# chassis_ctrl.net
KiCad netlist of a schematic drawn in EAGLE
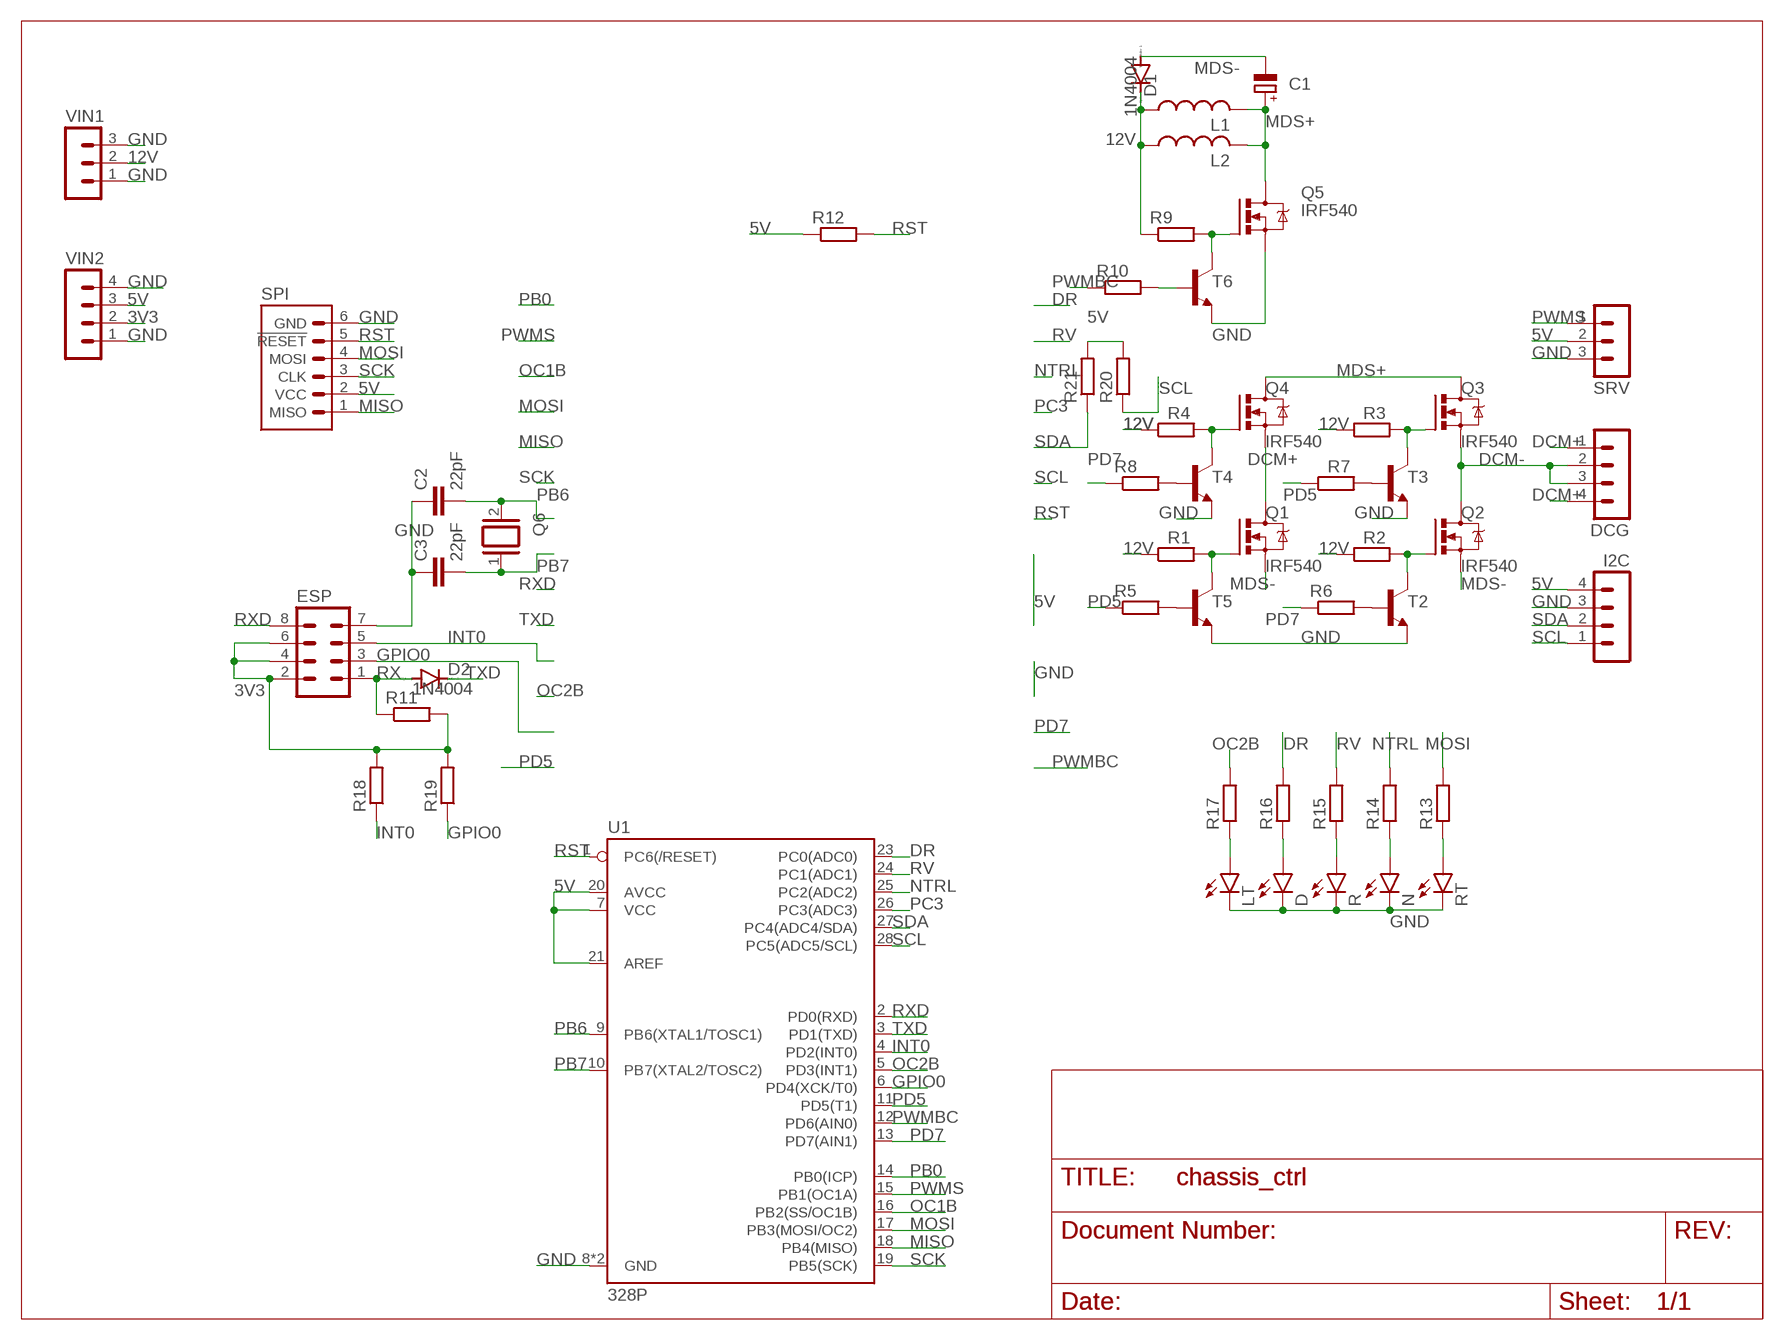
[diagram p0: schematic, sheet 1]

(export (version "E")
  (design (tool "Eeschema 10.0.6"))
  (components
    (comp (ref "C1")
      (value "CPOL-EUE5-10.5")
      (footprint "eagle-import:E5-10,5")
      (libsource (lib "eagle-import") (part "CPOL-EUE5-10.5"))
    )
    (comp (ref "C2")
      (value "22pF")
      (footprint "eagle-import:CAP-PTH-2.54")
      (libsource (lib "eagle-import") (part "22PF-PTH-2.54MM-200V-5%"))
    )
    (comp (ref "C3")
      (value "22pF")
      (footprint "eagle-import:CAP-PTH-2.54")
      (libsource (lib "eagle-import") (part "22PF-PTH-2.54MM-200V-5%"))
    )
    (comp (ref "D")
      (value "LED5MM")
      (footprint "eagle-import:LED5MM")
      (libsource (lib "eagle-import") (part "LED5MM"))
    )
    (comp (ref "D1")
      (value "1N4004")
      (footprint "eagle-import:DO41-10")
      (libsource (lib "eagle-import") (part "1N4004"))
    )
    (comp (ref "D2")
      (value "1N4004")
      (footprint "eagle-import:DO41-10")
      (libsource (lib "eagle-import") (part "1N4004"))
    )
    (comp (ref "DCG")
      (value "MA04-1")
      (footprint "eagle-import:MA04-1")
      (libsource (lib "eagle-import") (part "MA04-1"))
    )
    (comp (ref "ESP")
      (value "MA04-2")
      (footprint "eagle-import:MA04-2")
      (libsource (lib "eagle-import") (part "MA04-2"))
    )
    (comp (ref "I2C")
      (value "MA04-1")
      (footprint "eagle-import:MA04-1")
      (libsource (lib "eagle-import") (part "MA04-1"))
    )
    (comp (ref "L1")
      (value "L-US0204V")
      (footprint "eagle-import:0204V")
      (libsource (lib "eagle-import") (part "L-US0204V"))
    )
    (comp (ref "L2")
      (value "L-US0204V")
      (footprint "eagle-import:0204V")
      (libsource (lib "eagle-import") (part "L-US0204V"))
    )
    (comp (ref "LT")
      (value "LED5MM")
      (footprint "eagle-import:LED5MM")
      (libsource (lib "eagle-import") (part "LED5MM"))
    )
    (comp (ref "N")
      (value "LED5MM")
      (footprint "eagle-import:LED5MM")
      (libsource (lib "eagle-import") (part "LED5MM"))
    )
    (comp (ref "Q1")
      (value "IRF540")
      (footprint "eagle-import:TO220BV")
      (libsource (lib "eagle-import") (part "IRF540"))
    )
    (comp (ref "Q2")
      (value "IRF540")
      (footprint "eagle-import:TO220BV")
      (libsource (lib "eagle-import") (part "IRF540"))
    )
    (comp (ref "Q3")
      (value "IRF540")
      (footprint "eagle-import:TO220BV")
      (libsource (lib "eagle-import") (part "IRF540"))
    )
    (comp (ref "Q4")
      (value "IRF540")
      (footprint "eagle-import:TO220BV")
      (libsource (lib "eagle-import") (part "IRF540"))
    )
    (comp (ref "Q5")
      (value "IRF540")
      (footprint "eagle-import:TO220BV")
      (libsource (lib "eagle-import") (part "IRF540"))
    )
    (comp (ref "Q6")
      (value "XTAL/S")
      (footprint "eagle-import:QS")
      (libsource (lib "eagle-import") (part "XTAL/S"))
    )
    (comp (ref "R")
      (value "LED5MM")
      (footprint "eagle-import:LED5MM")
      (libsource (lib "eagle-import") (part "LED5MM"))
    )
    (comp (ref "R1")
      (value "R-EU_0207/10")
      (footprint "eagle-import:0207_10")
      (libsource (lib "eagle-import") (part "R-EU_0207/10"))
    )
    (comp (ref "R2")
      (value "R-EU_0207/10")
      (footprint "eagle-import:0207_10")
      (libsource (lib "eagle-import") (part "R-EU_0207/10"))
    )
    (comp (ref "R3")
      (value "R-EU_0207/10")
      (footprint "eagle-import:0207_10")
      (libsource (lib "eagle-import") (part "R-EU_0207/10"))
    )
    (comp (ref "R4")
      (value "R-EU_0207/10")
      (footprint "eagle-import:0207_10")
      (libsource (lib "eagle-import") (part "R-EU_0207/10"))
    )
    (comp (ref "R5")
      (value "R-EU_0207/10")
      (footprint "eagle-import:0207_10")
      (libsource (lib "eagle-import") (part "R-EU_0207/10"))
    )
    (comp (ref "R6")
      (value "R-EU_0207/10")
      (footprint "eagle-import:0207_10")
      (libsource (lib "eagle-import") (part "R-EU_0207/10"))
    )
    (comp (ref "R7")
      (value "R-EU_0207/10")
      (footprint "eagle-import:0207_10")
      (libsource (lib "eagle-import") (part "R-EU_0207/10"))
    )
    (comp (ref "R8")
      (value "R-EU_0207/10")
      (footprint "eagle-import:0207_10")
      (libsource (lib "eagle-import") (part "R-EU_0207/10"))
    )
    (comp (ref "R9")
      (value "R-EU_0207/10")
      (footprint "eagle-import:0207_10")
      (libsource (lib "eagle-import") (part "R-EU_0207/10"))
    )
    (comp (ref "R10")
      (value "R-EU_0207/10")
      (footprint "eagle-import:0207_10")
      (libsource (lib "eagle-import") (part "R-EU_0207/10"))
    )
    (comp (ref "R11")
      (value "R-EU_0207/10")
      (footprint "eagle-import:0207_10")
      (libsource (lib "eagle-import") (part "R-EU_0207/10"))
    )
    (comp (ref "R12")
      (value "R-EU_0207/10")
      (footprint "eagle-import:0207_10")
      (libsource (lib "eagle-import") (part "R-EU_0207/10"))
    )
    (comp (ref "R13")
      (value "R-EU_0207/10")
      (footprint "eagle-import:0207_10")
      (libsource (lib "eagle-import") (part "R-EU_0207/10"))
    )
    (comp (ref "R14")
      (value "R-EU_0207/10")
      (footprint "eagle-import:0207_10")
      (libsource (lib "eagle-import") (part "R-EU_0207/10"))
    )
    (comp (ref "R15")
      (value "R-EU_0207/10")
      (footprint "eagle-import:0207_10")
      (libsource (lib "eagle-import") (part "R-EU_0207/10"))
    )
    (comp (ref "R16")
      (value "R-EU_0207/10")
      (footprint "eagle-import:0207_10")
      (libsource (lib "eagle-import") (part "R-EU_0207/10"))
    )
    (comp (ref "R17")
      (value "R-EU_0207/10")
      (footprint "eagle-import:0207_10")
      (libsource (lib "eagle-import") (part "R-EU_0207/10"))
    )
    (comp (ref "R18")
      (value "R-EU_0207/10")
      (footprint "eagle-import:0207_10")
      (libsource (lib "eagle-import") (part "R-EU_0207/10"))
    )
    (comp (ref "R19")
      (value "R-EU_0207/10")
      (footprint "eagle-import:0207_10")
      (libsource (lib "eagle-import") (part "R-EU_0207/10"))
    )
    (comp (ref "R20")
      (value "R-EU_0207/10")
      (footprint "eagle-import:0207_10")
      (libsource (lib "eagle-import") (part "R-EU_0207/10"))
    )
    (comp (ref "R21")
      (value "R-EU_0207/10")
      (footprint "eagle-import:0207_10")
      (libsource (lib "eagle-import") (part "R-EU_0207/10"))
    )
    (comp (ref "RT")
      (value "LED5MM")
      (footprint "eagle-import:LED5MM")
      (libsource (lib "eagle-import") (part "LED5MM"))
    )
    (comp (ref "SPI")
      (value "MISO_MOSITHT_100MIL")
      (footprint "eagle-import:PINHEADER_2R03_100MIL")
      (libsource (lib "eagle-import") (part "MISO_MOSITHT_100MIL"))
    )
    (comp (ref "SRV")
      (value "MA03-1")
      (footprint "eagle-import:MA03-1")
      (libsource (lib "eagle-import") (part "MA03-1"))
    )
    (comp (ref "T2")
      (value "2N2222-NPN-TO92-EBC")
      (footprint "eagle-import:TO92-EBC")
      (libsource (lib "eagle-import") (part "-NPN-TO92-EBC2N2222"))
    )
    (comp (ref "T3")
      (value "2N2222-NPN-TO92-EBC")
      (footprint "eagle-import:TO92-EBC")
      (libsource (lib "eagle-import") (part "-NPN-TO92-EBC2N2222"))
    )
    (comp (ref "T4")
      (value "2N2222-NPN-TO92-EBC")
      (footprint "eagle-import:TO92-EBC")
      (libsource (lib "eagle-import") (part "-NPN-TO92-EBC2N2222"))
    )
    (comp (ref "T5")
      (value "2N2222-NPN-TO92-EBC")
      (footprint "eagle-import:TO92-EBC")
      (libsource (lib "eagle-import") (part "-NPN-TO92-EBC2N2222"))
    )
    (comp (ref "T6")
      (value "2N2222-NPN-TO92-EBC")
      (footprint "eagle-import:TO92-EBC")
      (libsource (lib "eagle-import") (part "-NPN-TO92-EBC2N2222"))
    )
    (comp (ref "U1")
      (value "328P")
      (footprint "eagle-import:DIP28")
      (libsource (lib "eagle-import") (part "ATMEGA328P_PDIP"))
    )
    (comp (ref "VIN1")
      (value "MA03-1")
      (footprint "eagle-import:MA03-1")
      (libsource (lib "eagle-import") (part "MA03-1"))
    )
    (comp (ref "VIN2")
      (value "MA04-1")
      (footprint "eagle-import:MA04-1")
      (libsource (lib "eagle-import") (part "MA04-1"))
    )
  )
  (nets
    (net (code "1") (name "/3V3") (class "Default")
      (node (ref "ESP") (pin "2") (pinfunction "2_2") (pintype "passive"))
      (node (ref "ESP") (pin "4") (pinfunction "4_4") (pintype "passive"))
      (node (ref "ESP") (pin "6") (pinfunction "6_6") (pintype "passive"))
      (node (ref "R11") (pin "2") (pinfunction "2_2") (pintype "passive"))
      (node (ref "R18") (pin "2") (pinfunction "2_2") (pintype "passive"))
      (node (ref "R19") (pin "2") (pinfunction "2_2") (pintype "passive"))
      (node (ref "VIN2") (pin "2") (pinfunction "2_2") (pintype "passive"))
    )
    (net (code "2") (name "/5V") (class "Default")
      (node (ref "I2C") (pin "4") (pinfunction "4_4") (pintype "passive"))
      (node (ref "R12") (pin "1") (pinfunction "1_1") (pintype "passive"))
      (node (ref "R20") (pin "2") (pinfunction "2_2") (pintype "passive"))
      (node (ref "R21") (pin "2") (pinfunction "2_2") (pintype "passive"))
      (node (ref "SPI") (pin "2") (pinfunction "VCC_2") (pintype "power_in"))
      (node (ref "SRV") (pin "2") (pinfunction "2_2") (pintype "passive"))
      (node (ref "U1") (pin "20") (pinfunction "AVCC_20") (pintype "bidirectional"))
      (node (ref "U1") (pin "21") (pinfunction "AREF_21") (pintype "bidirectional"))
      (node (ref "U1") (pin "7") (pinfunction "VCC_7") (pintype "bidirectional"))
      (node (ref "VIN2") (pin "3") (pinfunction "3_3") (pintype "passive"))
    )
    (net (code "3") (name "/12V") (class "Default")
      (node (ref "D1") (pin "C") (pinfunction "C_C") (pintype "passive"))
      (node (ref "L1") (pin "1") (pinfunction "1_1") (pintype "passive"))
      (node (ref "L2") (pin "1") (pinfunction "1_1") (pintype "passive"))
      (node (ref "R1") (pin "1") (pinfunction "1_1") (pintype "passive"))
      (node (ref "R2") (pin "1") (pinfunction "1_1") (pintype "passive"))
      (node (ref "R3") (pin "1") (pinfunction "1_1") (pintype "passive"))
      (node (ref "R4") (pin "1") (pinfunction "1_1") (pintype "passive"))
      (node (ref "R9") (pin "1") (pinfunction "1_1") (pintype "passive"))
      (node (ref "VIN1") (pin "2") (pinfunction "2_2") (pintype "passive"))
    )
    (net (code "4") (name "/DCM+") (class "Default")
      (node (ref "DCG") (pin "1") (pinfunction "1_1") (pintype "passive"))
      (node (ref "DCG") (pin "4") (pinfunction "4_4") (pintype "passive"))
      (node (ref "Q1") (pin "D") (pinfunction "D_D") (pintype "passive"))
      (node (ref "Q4") (pin "S") (pinfunction "S_S") (pintype "passive"))
    )
    (net (code "5") (name "/DCM-") (class "Default")
      (node (ref "DCG") (pin "2") (pinfunction "2_2") (pintype "passive"))
      (node (ref "DCG") (pin "3") (pinfunction "3_3") (pintype "passive"))
      (node (ref "Q2") (pin "D") (pinfunction "D_D") (pintype "passive"))
      (node (ref "Q3") (pin "S") (pinfunction "S_S") (pintype "passive"))
    )
    (net (code "6") (name "/DR") (class "Default")
      (node (ref "R16") (pin "2") (pinfunction "2_2") (pintype "passive"))
      (node (ref "U1") (pin "23") (pinfunction "PC0(ADC0)_23") (pintype "bidirectional"))
    )
    (net (code "7") (name "/GND") (class "Default")
      (node (ref "C2") (pin "1") (pinfunction "1_1") (pintype "passive"))
      (node (ref "C3") (pin "1") (pinfunction "1_1") (pintype "passive"))
      (node (ref "D") (pin "K") (pinfunction "C_K") (pintype "passive"))
      (node (ref "ESP") (pin "7") (pinfunction "7_7") (pintype "passive"))
      (node (ref "I2C") (pin "3") (pinfunction "3_3") (pintype "passive"))
      (node (ref "LT") (pin "K") (pinfunction "C_K") (pintype "passive"))
      (node (ref "N") (pin "K") (pinfunction "C_K") (pintype "passive"))
      (node (ref "Q5") (pin "S") (pinfunction "S_S") (pintype "passive"))
      (node (ref "R") (pin "K") (pinfunction "C_K") (pintype "passive"))
      (node (ref "RT") (pin "K") (pinfunction "C_K") (pintype "passive"))
      (node (ref "SPI") (pin "6") (pinfunction "GND_6") (pintype "power_in"))
      (node (ref "SRV") (pin "3") (pinfunction "3_3") (pintype "passive"))
      (node (ref "T2") (pin "E") (pinfunction "E_E") (pintype "passive"))
      (node (ref "T3") (pin "E") (pinfunction "E_E") (pintype "passive"))
      (node (ref "T4") (pin "E") (pinfunction "E_E") (pintype "passive"))
      (node (ref "T5") (pin "E") (pinfunction "E_E") (pintype "passive"))
      (node (ref "T6") (pin "E") (pinfunction "E_E") (pintype "passive"))
      (node (ref "U1") (pin "22") (pinfunction "GND_22") (pintype "bidirectional"))
      (node (ref "U1") (pin "8") (pinfunction "GND_8") (pintype "bidirectional"))
      (node (ref "VIN1") (pin "1") (pinfunction "1_1") (pintype "passive"))
      (node (ref "VIN1") (pin "3") (pinfunction "3_3") (pintype "passive"))
      (node (ref "VIN2") (pin "1") (pinfunction "1_1") (pintype "passive"))
      (node (ref "VIN2") (pin "4") (pinfunction "4_4") (pintype "passive"))
    )
    (net (code "8") (name "/GPIO0") (class "Default")
      (node (ref "ESP") (pin "3") (pinfunction "3_3") (pintype "passive"))
      (node (ref "R19") (pin "1") (pinfunction "1_1") (pintype "passive"))
      (node (ref "U1") (pin "6") (pinfunction "PD4(XCK/T0)_6") (pintype "bidirectional"))
    )
    (net (code "9") (name "/INT0") (class "Default")
      (node (ref "ESP") (pin "5") (pinfunction "5_5") (pintype "passive"))
      (node (ref "R18") (pin "1") (pinfunction "1_1") (pintype "passive"))
      (node (ref "U1") (pin "4") (pinfunction "PD2(INT0)_4") (pintype "bidirectional"))
    )
    (net (code "10") (name "/MDS+") (class "Default")
      (node (ref "C1") (pin "+") (pinfunction "+_+") (pintype "passive"))
      (node (ref "L1") (pin "2") (pinfunction "2_2") (pintype "passive"))
      (node (ref "L2") (pin "2") (pinfunction "2_2") (pintype "passive"))
      (node (ref "Q3") (pin "D") (pinfunction "D_D") (pintype "passive"))
      (node (ref "Q4") (pin "D") (pinfunction "D_D") (pintype "passive"))
      (node (ref "Q5") (pin "D") (pinfunction "D_D") (pintype "passive"))
    )
    (net (code "11") (name "/MDS-") (class "Default")
      (node (ref "C1") (pin "-") (pinfunction "-_-") (pintype "passive"))
      (node (ref "D1") (pin "A") (pinfunction "A_A") (pintype "passive"))
      (node (ref "Q1") (pin "S") (pinfunction "S_S") (pintype "passive"))
      (node (ref "Q2") (pin "S") (pinfunction "S_S") (pintype "passive"))
    )
    (net (code "12") (name "/MISO") (class "Default")
      (node (ref "SPI") (pin "1") (pinfunction "MISO_1") (pintype "passive"))
      (node (ref "U1") (pin "18") (pinfunction "PB4(MISO)_18") (pintype "bidirectional"))
    )
    (net (code "13") (name "/MOSI") (class "Default")
      (node (ref "R13") (pin "2") (pinfunction "2_2") (pintype "passive"))
      (node (ref "SPI") (pin "4") (pinfunction "MOSI_4") (pintype "passive"))
      (node (ref "U1") (pin "17") (pinfunction "PB3(MOSI/OC2)_17") (pintype "bidirectional"))
    )
    (net (code "14") (name "/NTRL") (class "Default")
      (node (ref "R14") (pin "2") (pinfunction "2_2") (pintype "passive"))
      (node (ref "U1") (pin "25") (pinfunction "PC2(ADC2)_25") (pintype "bidirectional"))
    )
    (net (code "15") (name "/OC1B") (class "Default")
      (node (ref "U1") (pin "16") (pinfunction "PB2(SS/OC1B)_16") (pintype "bidirectional"))
    )
    (net (code "16") (name "/OC2B") (class "Default")
      (node (ref "R17") (pin "2") (pinfunction "2_2") (pintype "passive"))
      (node (ref "U1") (pin "5") (pinfunction "PD3(INT1)_5") (pintype "bidirectional"))
    )
    (net (code "17") (name "/PB0") (class "Default")
      (node (ref "U1") (pin "14") (pinfunction "PB0(ICP)_14") (pintype "bidirectional"))
    )
    (net (code "18") (name "/PB6") (class "Default")
      (node (ref "C2") (pin "2") (pinfunction "2_2") (pintype "passive"))
      (node (ref "Q6") (pin "2") (pinfunction "2_2") (pintype "passive"))
      (node (ref "U1") (pin "9") (pinfunction "PB6(XTAL1/TOSC1)_9") (pintype "bidirectional"))
    )
    (net (code "19") (name "/PB7") (class "Default")
      (node (ref "C3") (pin "2") (pinfunction "2_2") (pintype "passive"))
      (node (ref "Q6") (pin "1") (pinfunction "1_1") (pintype "passive"))
      (node (ref "U1") (pin "10") (pinfunction "PB7(XTAL2/TOSC2)_10") (pintype "bidirectional"))
    )
    (net (code "20") (name "/PC3") (class "Default")
      (node (ref "U1") (pin "26") (pinfunction "PC3(ADC3)_26") (pintype "bidirectional"))
    )
    (net (code "21") (name "/PD5") (class "Default")
      (node (ref "R5") (pin "1") (pinfunction "1_1") (pintype "passive"))
      (node (ref "R7") (pin "1") (pinfunction "1_1") (pintype "passive"))
      (node (ref "U1") (pin "11") (pinfunction "PD5(T1)_11") (pintype "bidirectional"))
    )
    (net (code "22") (name "/PD7") (class "Default")
      (node (ref "R6") (pin "1") (pinfunction "1_1") (pintype "passive"))
      (node (ref "R8") (pin "1") (pinfunction "1_1") (pintype "passive"))
      (node (ref "U1") (pin "13") (pinfunction "PD7(AIN1)_13") (pintype "bidirectional"))
    )
    (net (code "23") (name "/PWMBC") (class "Default")
      (node (ref "R10") (pin "1") (pinfunction "1_1") (pintype "passive"))
      (node (ref "U1") (pin "12") (pinfunction "PD6(AIN0)_12") (pintype "bidirectional"))
    )
    (net (code "24") (name "/PWMS") (class "Default")
      (node (ref "SRV") (pin "1") (pinfunction "1_1") (pintype "passive"))
      (node (ref "U1") (pin "15") (pinfunction "PB1(OC1A)_15") (pintype "bidirectional"))
    )
    (net (code "25") (name "/RST") (class "Default")
      (node (ref "R12") (pin "2") (pinfunction "2_2") (pintype "passive"))
      (node (ref "SPI") (pin "5") (pinfunction "~{RESET}_5") (pintype "passive"))
      (node (ref "U1") (pin "1") (pinfunction "PC6(/RESET)_1") (pintype "bidirectional"))
    )
    (net (code "26") (name "/RV") (class "Default")
      (node (ref "R15") (pin "2") (pinfunction "2_2") (pintype "passive"))
      (node (ref "U1") (pin "24") (pinfunction "PC1(ADC1)_24") (pintype "bidirectional"))
    )
    (net (code "27") (name "/RX") (class "Default")
      (node (ref "D2") (pin "A") (pinfunction "A_A") (pintype "passive"))
      (node (ref "ESP") (pin "1") (pinfunction "1_1") (pintype "passive"))
      (node (ref "R11") (pin "1") (pinfunction "1_1") (pintype "passive"))
    )
    (net (code "28") (name "/RXD") (class "Default")
      (node (ref "ESP") (pin "8") (pinfunction "8_8") (pintype "passive"))
      (node (ref "U1") (pin "2") (pinfunction "PD0(RXD)_2") (pintype "bidirectional"))
    )
    (net (code "29") (name "/SCK") (class "Default")
      (node (ref "SPI") (pin "3") (pinfunction "CLK_3") (pintype "passive"))
      (node (ref "U1") (pin "19") (pinfunction "PB5(SCK)_19") (pintype "bidirectional"))
    )
    (net (code "30") (name "/SCL") (class "Default")
      (node (ref "I2C") (pin "1") (pinfunction "1_1") (pintype "passive"))
      (node (ref "R20") (pin "1") (pinfunction "1_1") (pintype "passive"))
      (node (ref "U1") (pin "28") (pinfunction "PC5(ADC5/SCL)_28") (pintype "bidirectional"))
    )
    (net (code "31") (name "/SDA") (class "Default")
      (node (ref "I2C") (pin "2") (pinfunction "2_2") (pintype "passive"))
      (node (ref "R21") (pin "1") (pinfunction "1_1") (pintype "passive"))
      (node (ref "U1") (pin "27") (pinfunction "PC4(ADC4/SDA)_27") (pintype "bidirectional"))
    )
    (net (code "32") (name "/TXD") (class "Default")
      (node (ref "D2") (pin "C") (pinfunction "C_C") (pintype "passive"))
      (node (ref "U1") (pin "3") (pinfunction "PD1(TXD)_3") (pintype "bidirectional"))
    )
    (net (code "33") (name "Net-(D-PadA)") (class "Default")
      (node (ref "D") (pin "A") (pinfunction "A_A") (pintype "passive"))
      (node (ref "R16") (pin "1") (pinfunction "1_1") (pintype "passive"))
    )
    (net (code "34") (name "Net-(LT-PadA)") (class "Default")
      (node (ref "LT") (pin "A") (pinfunction "A_A") (pintype "passive"))
      (node (ref "R17") (pin "1") (pinfunction "1_1") (pintype "passive"))
    )
    (net (code "35") (name "Net-(N-PadA)") (class "Default")
      (node (ref "N") (pin "A") (pinfunction "A_A") (pintype "passive"))
      (node (ref "R14") (pin "1") (pinfunction "1_1") (pintype "passive"))
    )
    (net (code "36") (name "Net-(Q1-PadG)") (class "Default")
      (node (ref "Q1") (pin "G") (pinfunction "G_G") (pintype "passive"))
      (node (ref "R1") (pin "2") (pinfunction "2_2") (pintype "passive"))
      (node (ref "T5") (pin "C") (pinfunction "C_C") (pintype "passive"))
    )
    (net (code "37") (name "Net-(Q2-PadG)") (class "Default")
      (node (ref "Q2") (pin "G") (pinfunction "G_G") (pintype "passive"))
      (node (ref "R2") (pin "2") (pinfunction "2_2") (pintype "passive"))
      (node (ref "T2") (pin "C") (pinfunction "C_C") (pintype "passive"))
    )
    (net (code "38") (name "Net-(Q3-PadG)") (class "Default")
      (node (ref "Q3") (pin "G") (pinfunction "G_G") (pintype "passive"))
      (node (ref "R3") (pin "2") (pinfunction "2_2") (pintype "passive"))
      (node (ref "T3") (pin "C") (pinfunction "C_C") (pintype "passive"))
    )
    (net (code "39") (name "Net-(Q4-PadG)") (class "Default")
      (node (ref "Q4") (pin "G") (pinfunction "G_G") (pintype "passive"))
      (node (ref "R4") (pin "2") (pinfunction "2_2") (pintype "passive"))
      (node (ref "T4") (pin "C") (pinfunction "C_C") (pintype "passive"))
    )
    (net (code "40") (name "Net-(Q5-PadG)") (class "Default")
      (node (ref "Q5") (pin "G") (pinfunction "G_G") (pintype "passive"))
      (node (ref "R9") (pin "2") (pinfunction "2_2") (pintype "passive"))
      (node (ref "T6") (pin "C") (pinfunction "C_C") (pintype "passive"))
    )
    (net (code "41") (name "Net-(R-PadA)") (class "Default")
      (node (ref "R") (pin "A") (pinfunction "A_A") (pintype "passive"))
      (node (ref "R15") (pin "1") (pinfunction "1_1") (pintype "passive"))
    )
    (net (code "42") (name "Net-(R5-Pad2)") (class "Default")
      (node (ref "R5") (pin "2") (pinfunction "2_2") (pintype "passive"))
      (node (ref "T5") (pin "B") (pinfunction "B_B") (pintype "passive"))
    )
    (net (code "43") (name "Net-(R6-Pad2)") (class "Default")
      (node (ref "R6") (pin "2") (pinfunction "2_2") (pintype "passive"))
      (node (ref "T2") (pin "B") (pinfunction "B_B") (pintype "passive"))
    )
    (net (code "44") (name "Net-(R7-Pad2)") (class "Default")
      (node (ref "R7") (pin "2") (pinfunction "2_2") (pintype "passive"))
      (node (ref "T3") (pin "B") (pinfunction "B_B") (pintype "passive"))
    )
    (net (code "45") (name "Net-(R8-Pad2)") (class "Default")
      (node (ref "R8") (pin "2") (pinfunction "2_2") (pintype "passive"))
      (node (ref "T4") (pin "B") (pinfunction "B_B") (pintype "passive"))
    )
    (net (code "46") (name "Net-(R10-Pad2)") (class "Default")
      (node (ref "R10") (pin "2") (pinfunction "2_2") (pintype "passive"))
      (node (ref "T6") (pin "B") (pinfunction "B_B") (pintype "passive"))
    )
    (net (code "47") (name "Net-(R13-Pad1)") (class "Default")
      (node (ref "R13") (pin "1") (pinfunction "1_1") (pintype "passive"))
      (node (ref "RT") (pin "A") (pinfunction "A_A") (pintype "passive"))
    )
  )
)
